# hovercraft.net
KiCad netlist of a schematic drawn in EAGLE
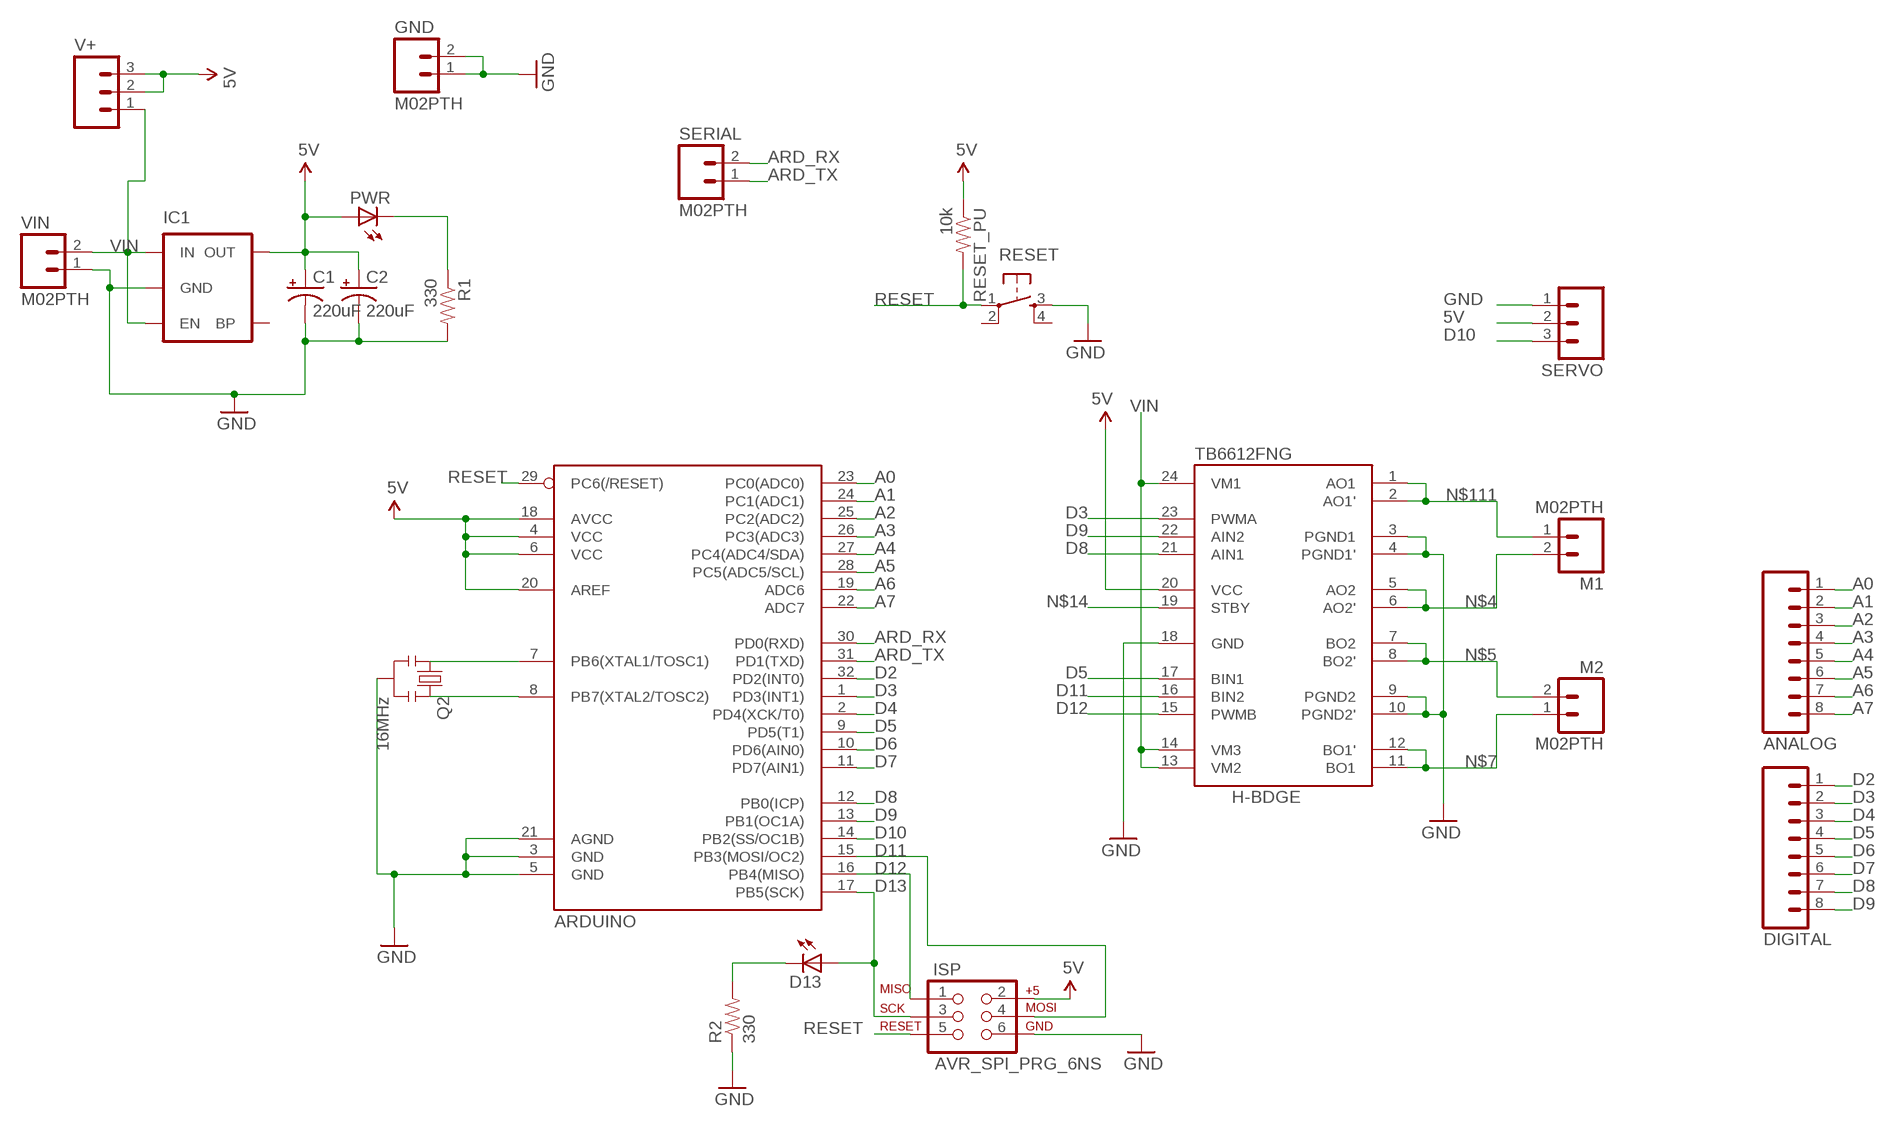
[diagram p0: schematic, sheet 1]

(export (version "E")
  (design (tool "Eeschema 10.0.6"))
  (components
    (comp (ref "ANALOG")
      (value "M08LOCK")
      (footprint "eagle-import:1X08_LOCK")
      (libsource (lib "eagle-import") (part "M08LOCK"))
    )
    (comp (ref "ARDUINO")
      (value "ATMEGA328_SMT")
      (footprint "eagle-import:TQFP32-08")
      (libsource (lib "eagle-import") (part "ATMEGA328_SMT"))
    )
    (comp (ref "C1")
      (value "220uF")
      (footprint "eagle-import:CPOL-RADIAL-100UF-25V")
      (libsource (lib "eagle-import") (part "CAP_POLPTH1"))
    )
    (comp (ref "C2")
      (value "220uF")
      (footprint "eagle-import:CPOL-RADIAL-100UF-25V")
      (libsource (lib "eagle-import") (part "CAP_POLPTH1"))
    )
    (comp (ref "D13")
      (value "LEDCHIPLED_0805")
      (footprint "eagle-import:CHIPLED_0805")
      (libsource (lib "eagle-import") (part "LEDCHIPLED_0805"))
    )
    (comp (ref "DIGITAL")
      (value "M08LOCK")
      (footprint "eagle-import:1X08_LOCK")
      (libsource (lib "eagle-import") (part "M08LOCK"))
    )
    (comp (ref "GND")
      (value "M02PTH")
      (footprint "eagle-import:1X02")
      (libsource (lib "eagle-import") (part "M02PTH"))
    )
    (comp (ref "H-BDGE")
      (value "TB6612FNG")
      (footprint "eagle-import:SSOP24")
      (libsource (lib "eagle-import") (part "TB6612FNG"))
    )
    (comp (ref "IC1")
      (value "MIC52055V")
      (footprint "eagle-import:SOT23-5")
      (libsource (lib "eagle-import") (part "MIC52055V"))
    )
    (comp (ref "ISP")
      (value "AVR_SPI_PRG_6NS")
      (footprint "eagle-import:2X3-NS")
      (libsource (lib "eagle-import") (part "AVR_SPI_PRG_6NS"))
    )
    (comp (ref "M1")
      (value "M02PTH")
      (footprint "eagle-import:1X02")
      (libsource (lib "eagle-import") (part "M02PTH"))
    )
    (comp (ref "M2")
      (value "M02PTH")
      (footprint "eagle-import:1X02")
      (libsource (lib "eagle-import") (part "M02PTH"))
    )
    (comp (ref "PWR")
      (value "LEDCHIPLED_0805")
      (footprint "eagle-import:CHIPLED_0805")
      (libsource (lib "eagle-import") (part "LEDCHIPLED_0805"))
    )
    (comp (ref "Q2")
      (value "16MHz")
      (footprint "eagle-import:RESONATOR-SMD")
      (libsource (lib "eagle-import") (part "RESONATOR16MHZ"))
    )
    (comp (ref "R1")
      (value "330")
      (footprint "eagle-import:0805")
      (libsource (lib "eagle-import") (part "RESISTOR0805-RES"))
    )
    (comp (ref "R2")
      (value "330")
      (footprint "eagle-import:0805")
      (libsource (lib "eagle-import") (part "RESISTOR0805-RES"))
    )
    (comp (ref "RESET")
      (value "TAC_SWITCHSMD")
      (footprint "eagle-import:TACTILE_SWITCH_SMD")
      (libsource (lib "eagle-import") (part "TAC_SWITCHSMD"))
    )
    (comp (ref "RESET_PU")
      (value "10k")
      (footprint "eagle-import:0805")
      (libsource (lib "eagle-import") (part "RESISTOR0805-RES"))
    )
    (comp (ref "SERIAL")
      (value "M02PTH")
      (footprint "eagle-import:1X02")
      (libsource (lib "eagle-import") (part "M02PTH"))
    )
    (comp (ref "SERVO")
      (value "M03PTH")
      (footprint "eagle-import:1X03")
      (libsource (lib "eagle-import") (part "M03PTH"))
    )
    (comp (ref "V+")
      (value "M03PTH")
      (footprint "eagle-import:1X03")
      (libsource (lib "eagle-import") (part "M03PTH"))
    )
    (comp (ref "VIN")
      (value "M02PTH")
      (footprint "eagle-import:1X02")
      (libsource (lib "eagle-import") (part "M02PTH"))
    )
  )
  (nets
    (net (code "1") (name "/A0") (class "Default")
      (node (ref "ANALOG") (pin "1") (pinfunction "1_1") (pintype "passive"))
      (node (ref "ARDUINO") (pin "23") (pinfunction "PC0(ADC0)_23") (pintype "bidirectional"))
    )
    (net (code "2") (name "/A1") (class "Default")
      (node (ref "ANALOG") (pin "2") (pinfunction "2_2") (pintype "passive"))
      (node (ref "ARDUINO") (pin "24") (pinfunction "PC1(ADC1)_24") (pintype "bidirectional"))
    )
    (net (code "3") (name "/A2") (class "Default")
      (node (ref "ANALOG") (pin "3") (pinfunction "3_3") (pintype "passive"))
      (node (ref "ARDUINO") (pin "25") (pinfunction "PC2(ADC2)_25") (pintype "bidirectional"))
    )
    (net (code "4") (name "/A3") (class "Default")
      (node (ref "ANALOG") (pin "4") (pinfunction "4_4") (pintype "passive"))
      (node (ref "ARDUINO") (pin "26") (pinfunction "PC3(ADC3)_26") (pintype "bidirectional"))
    )
    (net (code "5") (name "/A4") (class "Default")
      (node (ref "ANALOG") (pin "5") (pinfunction "5_5") (pintype "passive"))
      (node (ref "ARDUINO") (pin "27") (pinfunction "PC4(ADC4/SDA)_27") (pintype "bidirectional"))
    )
    (net (code "6") (name "/A5") (class "Default")
      (node (ref "ANALOG") (pin "6") (pinfunction "6_6") (pintype "passive"))
      (node (ref "ARDUINO") (pin "28") (pinfunction "PC5(ADC5/SCL)_28") (pintype "bidirectional"))
    )
    (net (code "7") (name "/A6") (class "Default")
      (node (ref "ANALOG") (pin "7") (pinfunction "7_7") (pintype "passive"))
      (node (ref "ARDUINO") (pin "19") (pinfunction "ADC6_19") (pintype "bidirectional"))
    )
    (net (code "8") (name "/A7") (class "Default")
      (node (ref "ANALOG") (pin "8") (pinfunction "8_8") (pintype "passive"))
      (node (ref "ARDUINO") (pin "22") (pinfunction "ADC7_22") (pintype "bidirectional"))
    )
    (net (code "9") (name "/ARD_RX") (class "Default")
      (node (ref "ARDUINO") (pin "30") (pinfunction "PD0(RXD)_30") (pintype "bidirectional"))
      (node (ref "SERIAL") (pin "2") (pinfunction "2_2") (pintype "passive"))
    )
    (net (code "10") (name "/ARD_TX") (class "Default")
      (node (ref "ARDUINO") (pin "31") (pinfunction "PD1(TXD)_31") (pintype "bidirectional"))
      (node (ref "SERIAL") (pin "1") (pinfunction "1_1") (pintype "passive"))
    )
    (net (code "11") (name "/D2") (class "Default")
      (node (ref "ARDUINO") (pin "32") (pinfunction "PD2(INT0)_32") (pintype "bidirectional"))
      (node (ref "DIGITAL") (pin "1") (pinfunction "1_1") (pintype "passive"))
    )
    (net (code "12") (name "/D3") (class "Default")
      (node (ref "ARDUINO") (pin "1") (pinfunction "PD3(INT1)_1") (pintype "bidirectional"))
      (node (ref "DIGITAL") (pin "2") (pinfunction "2_2") (pintype "passive"))
      (node (ref "H-BDGE") (pin "23") (pinfunction "PWMA_23") (pintype "input"))
    )
    (net (code "13") (name "/D4") (class "Default")
      (node (ref "ARDUINO") (pin "2") (pinfunction "PD4(XCK/T0)_2") (pintype "bidirectional"))
      (node (ref "DIGITAL") (pin "3") (pinfunction "3_3") (pintype "passive"))
    )
    (net (code "14") (name "/D5") (class "Default")
      (node (ref "ARDUINO") (pin "9") (pinfunction "PD5(T1)_9") (pintype "bidirectional"))
      (node (ref "DIGITAL") (pin "4") (pinfunction "4_4") (pintype "passive"))
      (node (ref "H-BDGE") (pin "17") (pinfunction "BIN1_17") (pintype "input"))
    )
    (net (code "15") (name "/D6") (class "Default")
      (node (ref "ARDUINO") (pin "10") (pinfunction "PD6(AIN0)_10") (pintype "bidirectional"))
      (node (ref "DIGITAL") (pin "5") (pinfunction "5_5") (pintype "passive"))
    )
    (net (code "16") (name "/D7") (class "Default")
      (node (ref "ARDUINO") (pin "11") (pinfunction "PD7(AIN1)_11") (pintype "bidirectional"))
      (node (ref "DIGITAL") (pin "6") (pinfunction "6_6") (pintype "passive"))
    )
    (net (code "17") (name "/D8") (class "Default")
      (node (ref "ARDUINO") (pin "12") (pinfunction "PB0(ICP)_12") (pintype "bidirectional"))
      (node (ref "DIGITAL") (pin "7") (pinfunction "7_7") (pintype "passive"))
      (node (ref "H-BDGE") (pin "21") (pinfunction "AIN1_21") (pintype "input"))
    )
    (net (code "18") (name "/D9") (class "Default")
      (node (ref "ARDUINO") (pin "13") (pinfunction "PB1(OC1A)_13") (pintype "bidirectional"))
      (node (ref "DIGITAL") (pin "8") (pinfunction "8_8") (pintype "passive"))
      (node (ref "H-BDGE") (pin "22") (pinfunction "AIN2_22") (pintype "input"))
    )
    (net (code "19") (name "/D10") (class "Default")
      (node (ref "ARDUINO") (pin "14") (pinfunction "PB2(SS/OC1B)_14") (pintype "bidirectional"))
      (node (ref "SERVO") (pin "3") (pinfunction "3_3") (pintype "passive"))
    )
    (net (code "20") (name "/D11") (class "Default")
      (node (ref "ARDUINO") (pin "15") (pinfunction "PB3(MOSI/OC2)_15") (pintype "bidirectional"))
      (node (ref "H-BDGE") (pin "16") (pinfunction "BIN2_16") (pintype "input"))
      (node (ref "ISP") (pin "4") (pinfunction "4_4") (pintype "passive"))
    )
    (net (code "21") (name "/D12") (class "Default")
      (node (ref "ARDUINO") (pin "16") (pinfunction "PB4(MISO)_16") (pintype "bidirectional"))
      (node (ref "H-BDGE") (pin "15") (pinfunction "PWMB_15") (pintype "input"))
      (node (ref "ISP") (pin "1") (pinfunction "1_1") (pintype "passive"))
    )
    (net (code "22") (name "/D13") (class "Default")
      (node (ref "ARDUINO") (pin "17") (pinfunction "PB5(SCK)_17") (pintype "bidirectional"))
      (node (ref "D13") (pin "A") (pinfunction "A_A") (pintype "passive"))
      (node (ref "ISP") (pin "3") (pinfunction "3_3") (pintype "passive"))
    )
    (net (code "23") (name "/N$4") (class "Default")
      (node (ref "H-BDGE") (pin "5") (pinfunction "AO2_5") (pintype "output"))
      (node (ref "H-BDGE") (pin "6") (pinfunction "AO2'_6") (pintype "output"))
      (node (ref "M1") (pin "2") (pinfunction "2_2") (pintype "passive"))
    )
    (net (code "24") (name "/N$5") (class "Default")
      (node (ref "H-BDGE") (pin "7") (pinfunction "BO2_7") (pintype "output"))
      (node (ref "H-BDGE") (pin "8") (pinfunction "BO2'_8") (pintype "output"))
      (node (ref "M2") (pin "2") (pinfunction "2_2") (pintype "passive"))
    )
    (net (code "25") (name "/N$7") (class "Default")
      (node (ref "H-BDGE") (pin "11") (pinfunction "BO1_11") (pintype "output"))
      (node (ref "H-BDGE") (pin "12") (pinfunction "BO1'_12") (pintype "output"))
      (node (ref "M2") (pin "1") (pinfunction "1_1") (pintype "passive"))
    )
    (net (code "26") (name "/N$14") (class "Default")
      (node (ref "H-BDGE") (pin "19") (pinfunction "STBY_19") (pintype "input"))
    )
    (net (code "27") (name "/N$111") (class "Default")
      (node (ref "H-BDGE") (pin "1") (pinfunction "AO1_1") (pintype "output"))
      (node (ref "H-BDGE") (pin "2") (pinfunction "AO1'_2") (pintype "output"))
      (node (ref "M1") (pin "1") (pinfunction "1_1") (pintype "passive"))
    )
    (net (code "28") (name "/RESET") (class "Default")
      (node (ref "ARDUINO") (pin "29") (pinfunction "PC6(/RESET)_29") (pintype "bidirectional"))
      (node (ref "ISP") (pin "5") (pinfunction "5_5") (pintype "passive"))
      (node (ref "RESET") (pin "1") (pinfunction "1_1") (pintype "passive"))
      (node (ref "RESET_PU") (pin "2") (pinfunction "2_2") (pintype "passive"))
    )
    (net (code "29") (name "/VIN") (class "Default")
      (node (ref "H-BDGE") (pin "13") (pinfunction "VM2_13") (pintype "power_in"))
      (node (ref "H-BDGE") (pin "14") (pinfunction "VM3_14") (pintype "power_in"))
      (node (ref "H-BDGE") (pin "24") (pinfunction "VM1_24") (pintype "power_in"))
      (node (ref "IC1") (pin "1") (pinfunction "IN_1") (pintype "input"))
      (node (ref "IC1") (pin "3") (pinfunction "EN_3") (pintype "input"))
      (node (ref "V+") (pin "1") (pinfunction "1_1") (pintype "passive"))
      (node (ref "VIN") (pin "2") (pinfunction "2_2") (pintype "passive"))
    )
    (net (code "30") (name "5V") (class "Default")
      (node (ref "ARDUINO") (pin "18") (pinfunction "AVCC_18") (pintype "bidirectional"))
      (node (ref "ARDUINO") (pin "20") (pinfunction "AREF_20") (pintype "bidirectional"))
      (node (ref "ARDUINO") (pin "4") (pinfunction "VCC_4") (pintype "bidirectional"))
      (node (ref "ARDUINO") (pin "6") (pinfunction "VCC_6") (pintype "bidirectional"))
      (node (ref "C1") (pin "1") (pinfunction "+_1") (pintype "passive"))
      (node (ref "C2") (pin "1") (pinfunction "+_1") (pintype "passive"))
      (node (ref "H-BDGE") (pin "20") (pinfunction "VCC_20") (pintype "power_in"))
      (node (ref "IC1") (pin "5") (pinfunction "OUT_5") (pintype "passive"))
      (node (ref "ISP") (pin "2") (pinfunction "2_2") (pintype "passive"))
      (node (ref "PWR") (pin "A") (pinfunction "A_A") (pintype "passive"))
      (node (ref "RESET_PU") (pin "1") (pinfunction "1_1") (pintype "passive"))
      (node (ref "SERVO") (pin "2") (pinfunction "2_2") (pintype "passive"))
      (node (ref "V+") (pin "2") (pinfunction "2_2") (pintype "passive"))
      (node (ref "V+") (pin "3") (pinfunction "3_3") (pintype "passive"))
    )
    (net (code "31") (name "GND") (class "Default")
      (node (ref "ARDUINO") (pin "21") (pinfunction "AGND_21") (pintype "bidirectional"))
      (node (ref "ARDUINO") (pin "3") (pinfunction "GND_3") (pintype "bidirectional"))
      (node (ref "ARDUINO") (pin "5") (pinfunction "GND_5") (pintype "bidirectional"))
      (node (ref "C1") (pin "2") (pinfunction "-_2") (pintype "passive"))
      (node (ref "C2") (pin "2") (pinfunction "-_2") (pintype "passive"))
      (node (ref "GND") (pin "1") (pinfunction "1_1") (pintype "passive"))
      (node (ref "GND") (pin "2") (pinfunction "2_2") (pintype "passive"))
      (node (ref "H-BDGE") (pin "10") (pinfunction "PGND2'_10") (pintype "power_in"))
      (node (ref "H-BDGE") (pin "18") (pinfunction "GND_18") (pintype "power_in"))
      (node (ref "H-BDGE") (pin "3") (pinfunction "PGND1_3") (pintype "power_in"))
      (node (ref "H-BDGE") (pin "4") (pinfunction "PGND1'_4") (pintype "power_in"))
      (node (ref "H-BDGE") (pin "9") (pinfunction "PGND2_9") (pintype "power_in"))
      (node (ref "IC1") (pin "2") (pinfunction "GND_2") (pintype "input"))
      (node (ref "ISP") (pin "6") (pinfunction "6_6") (pintype "passive"))
      (node (ref "Q2") (pin "2") (pinfunction "2_2") (pintype "passive"))
      (node (ref "R1") (pin "2") (pinfunction "2_2") (pintype "passive"))
      (node (ref "R2") (pin "1") (pinfunction "1_1") (pintype "passive"))
      (node (ref "RESET") (pin "3") (pinfunction "3_3") (pintype "passive"))
      (node (ref "SERVO") (pin "1") (pinfunction "1_1") (pintype "passive"))
      (node (ref "VIN") (pin "1") (pinfunction "1_1") (pintype "passive"))
    )
    (net (code "32") (name "Net-(ARDUINO-PB6(XTAL1{slash}TOSC1))") (class "Default")
      (node (ref "ARDUINO") (pin "7") (pinfunction "PB6(XTAL1/TOSC1)_7") (pintype "bidirectional"))
      (node (ref "Q2") (pin "1") (pinfunction "1_1") (pintype "passive"))
    )
    (net (code "33") (name "Net-(ARDUINO-PB7(XTAL2{slash}TOSC2))") (class "Default")
      (node (ref "ARDUINO") (pin "8") (pinfunction "PB7(XTAL2/TOSC2)_8") (pintype "bidirectional"))
      (node (ref "Q2") (pin "3") (pinfunction "3_3") (pintype "passive"))
    )
    (net (code "34") (name "Net-(D13-PadC)") (class "Default")
      (node (ref "D13") (pin "C") (pinfunction "C_C") (pintype "passive"))
      (node (ref "R2") (pin "2") (pinfunction "2_2") (pintype "passive"))
    )
    (net (code "35") (name "Net-(PWR-PadC)") (class "Default")
      (node (ref "PWR") (pin "C") (pinfunction "C_C") (pintype "passive"))
      (node (ref "R1") (pin "1") (pinfunction "1_1") (pintype "passive"))
    )
    (net (code "36") (name "unconnected-(IC1-BP-Pad4)") (class "Default")
      (node (ref "IC1") (pin "4") (pinfunction "BP_4") (pintype "input"))
    )
    (net (code "37") (name "unconnected-(RESET-Pad2)") (class "Default")
      (node (ref "RESET") (pin "2") (pinfunction "2_2") (pintype "passive"))
    )
    (net (code "38") (name "unconnected-(RESET-Pad4)") (class "Default")
      (node (ref "RESET") (pin "4") (pinfunction "4_4") (pintype "passive"))
    )
  )
)
